# LoRa_Bee.net
KiCad netlist of a schematic drawn in EAGLE
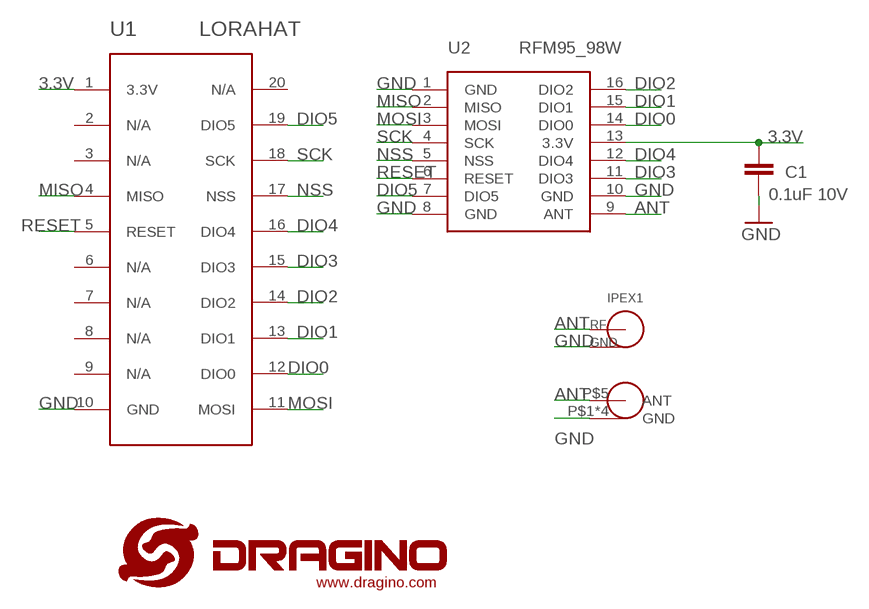
[diagram p0: schematic, sheet 1]

(export (version "E")
  (design (tool "Eeschema 10.0.6"))
  (components
    (comp (ref "C1")
      (value "0.1uF 10V")
      (footprint "eagle-import:C0402")
      (libsource (lib "eagle-import") (part "C-EUC0402"))
    )
    (comp (ref "IPEX1")
      (value "I-PEX")
      (footprint "eagle-import:I-PEX")
      (libsource (lib "eagle-import") (part "I-PEX"))
    )
    (comp (ref "U$1")
      (value "LOGO-NEW")
      (footprint "eagle-import:LOGO-SILK-NEW")
      (libsource (lib "eagle-import") (part "LOGO-NEW"))
    )
    (comp (ref "U1")
      (value "LORAHAT")
      (footprint "eagle-import:LORAHAT")
      (libsource (lib "eagle-import") (part "LORAHAT"))
    )
    (comp (ref "U2")
      (value "RFM95_98W")
      (footprint "eagle-import:RFM95_98W")
      (libsource (lib "eagle-import") (part "RFM95_98W"))
    )
    (comp (ref "X4")
      (value "SMA-KE")
      (footprint "eagle-import:SMA-KE")
      (libsource (lib "eagle-import") (part "SMA-KE"))
    )
  )
  (nets
    (net (code "1") (name "/3.3V") (class "Default")
      (node (ref "C1") (pin "2") (pinfunction "2_2") (pintype "passive"))
      (node (ref "U1") (pin "1") (pinfunction "3.3V_1") (pintype "bidirectional"))
      (node (ref "U2") (pin "13") (pinfunction "3.3V_13") (pintype "power_in"))
    )
    (net (code "2") (name "/ANT") (class "Default")
      (node (ref "IPEX1") (pin "SIG") (pinfunction "SIG_SIG") (pintype "passive"))
      (node (ref "U2") (pin "9") (pinfunction "ANT_9") (pintype "bidirectional"))
      (node (ref "X4") (pin "P$5") (pinfunction "ANT_P$5") (pintype "bidirectional"))
    )
    (net (code "3") (name "/DIO0") (class "Default")
      (node (ref "U1") (pin "12") (pinfunction "DIO0_12") (pintype "bidirectional"))
      (node (ref "U2") (pin "14") (pinfunction "DIO0_14") (pintype "bidirectional"))
    )
    (net (code "4") (name "/DIO1") (class "Default")
      (node (ref "U1") (pin "13") (pinfunction "DIO1_13") (pintype "bidirectional"))
      (node (ref "U2") (pin "15") (pinfunction "DIO1_15") (pintype "bidirectional"))
    )
    (net (code "5") (name "/DIO2") (class "Default")
      (node (ref "U1") (pin "14") (pinfunction "DIO2_14") (pintype "bidirectional"))
      (node (ref "U2") (pin "16") (pinfunction "DIO2_16") (pintype "bidirectional"))
    )
    (net (code "6") (name "/DIO3") (class "Default")
      (node (ref "U1") (pin "15") (pinfunction "DIO3_15") (pintype "bidirectional"))
      (node (ref "U2") (pin "11") (pinfunction "DIO3_11") (pintype "bidirectional"))
    )
    (net (code "7") (name "/DIO4") (class "Default")
      (node (ref "U1") (pin "16") (pinfunction "DIO4_16") (pintype "bidirectional"))
      (node (ref "U2") (pin "12") (pinfunction "DIO4_12") (pintype "bidirectional"))
    )
    (net (code "8") (name "/DIO5") (class "Default")
      (node (ref "U1") (pin "19") (pinfunction "DIO5_19") (pintype "bidirectional"))
      (node (ref "U2") (pin "7") (pinfunction "DIO5_7") (pintype "bidirectional"))
    )
    (net (code "9") (name "/MISO") (class "Default")
      (node (ref "U1") (pin "4") (pinfunction "MISO_4") (pintype "bidirectional"))
      (node (ref "U2") (pin "2") (pinfunction "MISO_2") (pintype "bidirectional"))
    )
    (net (code "10") (name "/MOSI") (class "Default")
      (node (ref "U1") (pin "11") (pinfunction "MOSI_11") (pintype "bidirectional"))
      (node (ref "U2") (pin "3") (pinfunction "MOSI_3") (pintype "bidirectional"))
    )
    (net (code "11") (name "/NSS") (class "Default")
      (node (ref "U1") (pin "17") (pinfunction "NSS_17") (pintype "bidirectional"))
      (node (ref "U2") (pin "5") (pinfunction "NSS_5") (pintype "bidirectional"))
    )
    (net (code "12") (name "/RESET") (class "Default")
      (node (ref "U1") (pin "5") (pinfunction "RESET_5") (pintype "bidirectional"))
      (node (ref "U2") (pin "6") (pinfunction "RESET_6") (pintype "bidirectional"))
    )
    (net (code "13") (name "/SCK") (class "Default")
      (node (ref "U1") (pin "18") (pinfunction "SCK_18") (pintype "bidirectional"))
      (node (ref "U2") (pin "4") (pinfunction "SCK_4") (pintype "bidirectional"))
    )
    (net (code "14") (name "GND") (class "Default")
      (node (ref "C1") (pin "1") (pinfunction "1_1") (pintype "passive"))
      (node (ref "IPEX1") (pin "GND") (pinfunction "GND_GND") (pintype "passive"))
      (node (ref "IPEX1") (pin "GND1") (pinfunction "GND_GND1") (pintype "passive"))
      (node (ref "U1") (pin "10") (pinfunction "GND_10") (pintype "bidirectional"))
      (node (ref "U2") (pin "1") (pinfunction "GND_1") (pintype "power_in"))
      (node (ref "U2") (pin "10") (pinfunction "GND_10") (pintype "power_in"))
      (node (ref "U2") (pin "8") (pinfunction "GND_8") (pintype "power_in"))
      (node (ref "X4") (pin "P$1") (pinfunction "GND_P$1") (pintype "bidirectional"))
      (node (ref "X4") (pin "P$2") (pinfunction "GND_P$2") (pintype "bidirectional"))
      (node (ref "X4") (pin "P$3") (pinfunction "GND_P$3") (pintype "bidirectional"))
      (node (ref "X4") (pin "P$4") (pinfunction "GND_P$4") (pintype "bidirectional"))
    )
    (net (code "15") (name "unconnected-(U1-N{slash}A-Pad2)") (class "Default")
      (node (ref "U1") (pin "2") (pinfunction "N/A_2") (pintype "bidirectional"))
    )
    (net (code "16") (name "unconnected-(U1-N{slash}A-Pad3)") (class "Default")
      (node (ref "U1") (pin "3") (pinfunction "N/A_3") (pintype "bidirectional"))
    )
    (net (code "17") (name "unconnected-(U1-N{slash}A-Pad6)") (class "Default")
      (node (ref "U1") (pin "6") (pinfunction "N/A_6") (pintype "bidirectional"))
    )
    (net (code "18") (name "unconnected-(U1-N{slash}A-Pad7)") (class "Default")
      (node (ref "U1") (pin "7") (pinfunction "N/A_7") (pintype "bidirectional"))
    )
    (net (code "19") (name "unconnected-(U1-N{slash}A-Pad8)") (class "Default")
      (node (ref "U1") (pin "8") (pinfunction "N/A_8") (pintype "bidirectional"))
    )
    (net (code "20") (name "unconnected-(U1-N{slash}A-Pad9)") (class "Default")
      (node (ref "U1") (pin "9") (pinfunction "N/A_9") (pintype "bidirectional"))
    )
    (net (code "21") (name "unconnected-(U1-N{slash}A-Pad20)") (class "Default")
      (node (ref "U1") (pin "20") (pinfunction "N/A_20") (pintype "bidirectional"))
    )
  )
)
